# 5V5to3V3Buck.net
KiCad netlist of a schematic drawn in Altium Designer
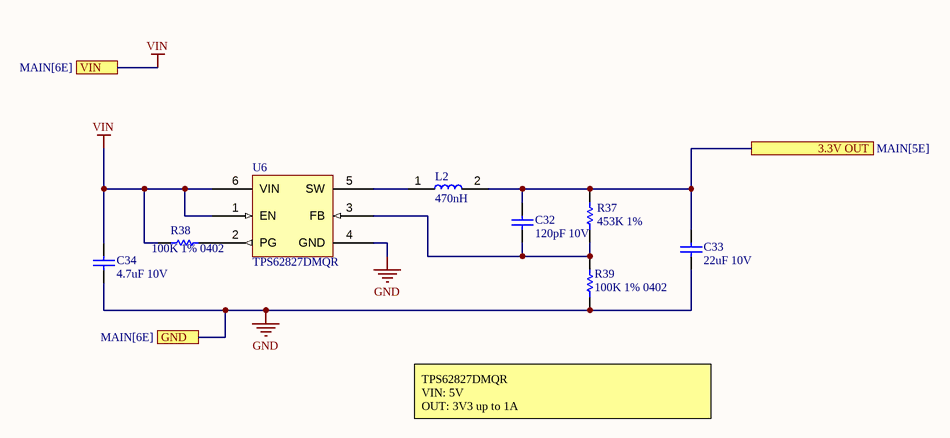
[diagram p0: 5V5to3V3Buck.SchDoc]

(export (version "E")
  (design (tool "Eeschema 10.0.6"))
  (components
    (comp (ref "C32")
      (value "120pF 10V")
      (footprint "CAPC0603(1608)100_N")
      (description "CAP 120pF 10V ±10% 0603 (1608 Metric) Thickness 1mm SMD")
      (fields (field (name "TOLERANCE") "Â±10%"))
      (libsource (lib "Altium Content Vault") (part "CAP"))
    )
    (comp (ref "C33")
      (value "22uF 10V")
      (footprint "CAPC1608X100X20ML10")
      (description "Chip Capacitor, 22 uF, +/- 20%, 10 V, -55 to 85 degC, 0603 (1608 Metric), RoHS, Tape and Reel")
      (fields (field (name "MANUFACTURER") "TDK") (field (name "TOLERANCE") "±20%"))
      (libsource (lib "Altium Content Vault") (part "CAP-NP-2"))
    )
    (comp (ref "C34")
      (value "4.7uF 10V")
      (footprint "CAPC0603(1608)55_N")
      (description "CAP 4.7uF 10V ±10% 0603 (1608 Metric) Thickness 0.55mm SMD")
      (fields (field (name "TOLERANCE") "Â±10%"))
      (libsource (lib "Altium Content Vault") (part "CAP"))
    )
    (comp (ref "L2")
      (value "470nH")
      (footprint "MLP2012SR47MT0S1")
      (description "FIXED IND 470NH 1.2A 90 MOHM SMD")
      (fields (field (name "MP") "MLP2012SR47MT0S1") (field (name "MANUFACTURER") "TDK"))
      (libsource (lib "ESE516A2") (part "MLP2012SR47MT0S1"))
    )
    (comp (ref "R37")
      (value "453K 1%")
      (footprint "RESC0402(1005)_L")
      (description "453K 0.063W 1% 0402 (1005 Metric)  SMD")
      (fields (field (name "TOLERANCE") "1 %") (field (name "POWER") "0.063 W"))
      (libsource (lib "Altium Content Vault") (part "RES"))
    )
    (comp (ref "R38")
      (value "100K 1% 0402")
      (footprint "RESC0402(1005)_M")
      (description "100K 0.063W 1% 0402 (1005 Metric)  SMD")
      (fields (field (name "POWER") "0.063 W") (field (name "TOLERANCE") "1 %"))
      (libsource (lib "Altium Content Vault") (part "RES"))
    )
    (comp (ref "R39")
      (value "100K 1% 0402")
      (footprint "RESC0402(1005)_M")
      (description "100K 0.063W 1% 0402 (1005 Metric)  SMD")
      (fields (field (name "POWER") "0.063 W") (field (name "TOLERANCE") "1 %"))
      (libsource (lib "Altium Content Vault") (part "RES"))
    )
    (comp (ref "U6")
      (value "TPS62827DMQR")
      (footprint "Texas_Instruments_DMQ0006A_MFG")
      (description "2.4V-5.5V input, 4A step-down converter with 1% Accuracy in 1.5mm x 1.5mm QFN 6-VSON-HR -40 to 125")
      (fields (field (name "MANUFACTURER") "Texas Instruments"))
      (libsource (lib "ESE516A2") (part "TPS62827DMQR"))
    )
  )
  (nets
    (net (code "1") (name "/3.3V OUT") (class "Default")
      (node (ref "C32") (pin "2") (pinfunction "2_2") (pintype "passive"))
      (node (ref "C33") (pin "2") (pinfunction "2_2") (pintype "passive"))
      (node (ref "L2") (pin "2") (pinfunction "2_2") (pintype "passive"))
      (node (ref "R37") (pin "1") (pinfunction "1_1") (pintype "passive"))
    )
    (net (code "2") (name "GND") (class "Default")
      (node (ref "C33") (pin "1") (pinfunction "1_1") (pintype "passive"))
      (node (ref "C34") (pin "1") (pinfunction "1_1") (pintype "passive"))
      (node (ref "R39") (pin "1") (pinfunction "1_1") (pintype "passive"))
      (node (ref "U6") (pin "4") (pinfunction "GND_4") (pintype "power_in"))
    )
    (net (code "3") (name "Net-(U6-FB)") (class "Default")
      (node (ref "C32") (pin "1") (pinfunction "1_1") (pintype "passive"))
      (node (ref "R37") (pin "2") (pinfunction "2_2") (pintype "passive"))
      (node (ref "R39") (pin "2") (pinfunction "2_2") (pintype "passive"))
      (node (ref "U6") (pin "3") (pinfunction "FB_3") (pintype "input"))
    )
    (net (code "4") (name "Net-(U6-PG)") (class "Default")
      (node (ref "R38") (pin "2") (pinfunction "2_2") (pintype "passive"))
      (node (ref "U6") (pin "2") (pinfunction "PG_2") (pintype "output"))
    )
    (net (code "5") (name "Net-(U6-SW)") (class "Default")
      (node (ref "L2") (pin "1") (pinfunction "1_1") (pintype "passive"))
      (node (ref "U6") (pin "5") (pinfunction "SW_5") (pintype "power_in"))
    )
    (net (code "6") (name "VIN") (class "Default")
      (node (ref "C34") (pin "2") (pinfunction "2_2") (pintype "passive"))
      (node (ref "R38") (pin "1") (pinfunction "1_1") (pintype "passive"))
      (node (ref "U6") (pin "1") (pinfunction "EN_1") (pintype "input"))
      (node (ref "U6") (pin "6") (pinfunction "VIN_6") (pintype "power_in"))
    )
  )
)
